# Sheet1.net
KiCad netlist of a schematic drawn in Altium Designer
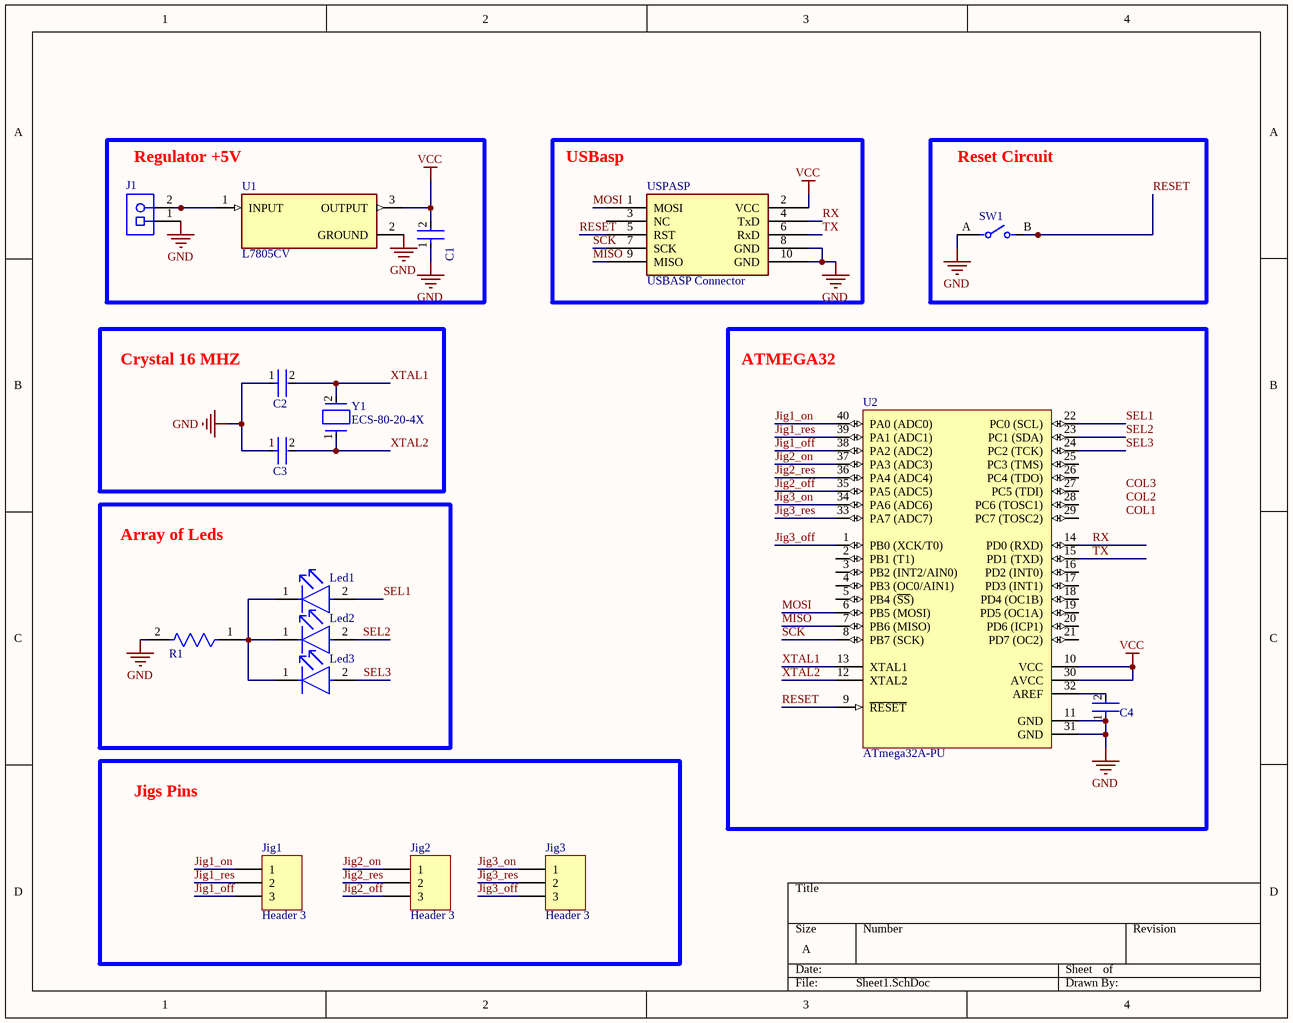
[diagram p0: Sheet1.SchDoc]

(export (version "E")
  (design (tool "Eeschema 10.0.6"))
  (components
    (comp (ref "C1")
      (value "K103K15X7RF5TL2")
      (footprint "FP-K155L2-MFG")
      (description "K103K15X7RF5TL2 Multilayer Ceramic Capacitor, 0.01 uF, 50 V, ± 10%, X7R, Radial Leaded")
      (fields (field (name "VOLTAGE") "50V") (field (name "TOLERANCE") "10%"))
      (libsource (lib "Altium Content Vault") (part "02cd4be3c70576c341d710602a673aa"))
    )
    (comp (ref "C2")
      (value "K103K15X7RF5TL2")
      (footprint "FP-K155L2-MFG")
      (description "K103K15X7RF5TL2 Multilayer Ceramic Capacitor, 0.01 uF, 50 V, ± 10%, X7R, Radial Leaded (10P)")
      (fields (field (name "VOLTAGE") "50V") (field (name "TOLERANCE") "10%"))
      (libsource (lib "Altium Content Vault") (part "02cd4be3c70576c341d710602a673aa"))
    )
    (comp (ref "C3")
      (value "K103K15X7RF5TL2")
      (footprint "FP-K155L2-MFG")
      (description "K103K15X7RF5TL2 Multilayer Ceramic Capacitor, 0.01 uF, 50 V, ± 10%, X7R, Radial Leaded (10P)")
      (fields (field (name "VOLTAGE") "50V") (field (name "TOLERANCE") "10%"))
      (libsource (lib "Altium Content Vault") (part "02cd4be3c70576c341d710602a673aa"))
    )
    (comp (ref "C4")
      (value "K103K15X7RF5TL2")
      (footprint "FP-K155L2-MFG")
      (description "K103K15X7RF5TL2 Multilayer Ceramic Capacitor, 0.01 uF, 50 V, ± 10%, X7R, Radial Leaded")
      (fields (field (name "VOLTAGE") "50V") (field (name "TOLERANCE") "10%"))
      (libsource (lib "Altium Content Vault") (part "02cd4be3c70576c341d710602a673aa"))
    )
    (comp (ref "J1")
      (value "1729128")
      (footprint "PHOE-1729128-2_V")
      (description "Header of  Input Batt")
      (fields (field (name "MANUFACTURER") "Phoenix Contact"))
      (libsource (lib "Altium Content Vault") (part "CN-2P-F-R2"))
    )
    (comp (ref "Jig1")
      (value "Header 3")
      (footprint "HDR1X3")
      (description "Header, 3-Pin")
      (fields (field (name "PUBLISHER") "Altium Limited"))
      (libsource (lib "Miscellaneous+Connectors") (part "Header 3"))
    )
    (comp (ref "Jig2")
      (value "Header 3")
      (footprint "HDR1X3")
      (description "Header, 3-Pin")
      (fields (field (name "PUBLISHER") "Altium Limited"))
      (libsource (lib "Miscellaneous+Connectors") (part "Header 3"))
    )
    (comp (ref "Jig3")
      (value "Header 3")
      (footprint "HDR1X3")
      (description "Header, 3-Pin")
      (fields (field (name "PUBLISHER") "Altium Limited"))
      (libsource (lib "Miscellaneous+Connectors") (part "Header 3"))
    )
    (comp (ref "Led1")
      (value "TLLG4401")
      (footprint "FP-6_544-5255_01-4-MFG")
      (description "TLLG4401 LED, Green, 2mcd, 3mmDia., T-1, +/-25deg, 565nm, 7mA, 1.9V Vf, 20V Vr, 20mW, -40")
      (libsource (lib "Altium Content Vault") (part "8706943c75ba83719d021d2fdc84c58"))
    )
    (comp (ref "Led2")
      (value "TLLG4401")
      (footprint "FP-6_544-5255_01-4-MFG")
      (description "TLLG4401 LED, Green, 2mcd, 3mmDia., T-1, +/-25deg, 565nm, 7mA, 1.9V Vf, 20V Vr, 20mW, -40")
      (libsource (lib "Altium Content Vault") (part "8706943c75ba83719d021d2fdc84c58"))
    )
    (comp (ref "Led3")
      (value "TLLG4401")
      (footprint "FP-6_544-5255_01-4-MFG")
      (description "TLLG4401 LED, Green, 2mcd, 3mmDia., T-1, +/-25deg, 565nm, 7mA, 1.9V Vf, 20V Vr, 20mW, -40")
      (libsource (lib "Altium Content Vault") (part "8706943c75ba83719d021d2fdc84c58"))
    )
    (comp (ref "R1")
      (value "MRS25000C1001FCT00")
      (footprint "FP-MRS25-MFG")
      (description "RES 1K OHM 0.6W 1% for all leds")
      (fields (field (name "TOLERANCE") "1%"))
      (libsource (lib "Altium Content Vault") (part "1029c3af85768c4190bb7ad29bc67b5"))
    )
    (comp (ref "SW1")
      (value "EVQ-21505R")
      (footprint "FP-EVQ-21505R-MFG")
      (description "Switch for reset circuits")
      (libsource (lib "Altium Content Vault") (part "2b0b2b19372efd94fa7681498149756"))
    )
    (comp (ref "U1")
      (value "L7805CV")
      (footprint "TO255P1040X460X1968-3")
      (description "Linear Voltage Regulator IC Positive Fixed 1 Output 1.5A TO-220")
      (fields (field (name "MF") "STMicroelectronics"))
      (libsource (lib "L7805CV") (part "L7805CV"))
    )
    (comp (ref "U2")
      (value "ATmega32A-PU")
      (footprint "40P6")
      (libsource (lib "Altium Content Vault") (part "MC-8B-AT16A-IL40"))
    )
    (comp (ref "USPASP")
      (value "USBASP Connector")
      (footprint "SHDR10W99P254_2X5_2032X889X927P")
      (description "Connector")
      (fields
        (field (name "MANUFACTURER_PART_NUMBER") "70246-1001")
        (field (name "MOUSER PART NUMBER") "538-70246-1001")
      )
      (libsource (lib "YoussifLIB") (part "USBASP Connector"))
    )
    (comp (ref "Y1")
      (value "ECS-80-20-4X")
      (footprint "FP-ECS-80-20-4X-MFG")
      (fields (field (name "TOLERANCE") "0.003%"))
      (libsource (lib "Altium Content Vault") (part "c23a69dc6c9e2f18f2079038eb95dd1"))
    )
  )
  (nets
    (net (code "4") (name "/Jig1_off") (class "Default")
      (node (ref "Jig1") (pin "3") (pinfunction "3_3") (pintype "passive"))
      (node (ref "U2") (pin "38") (pinfunction "PA2_(ADC2)_38") (pintype "bidirectional"))
    )
    (net (code "5") (name "/Jig1_on") (class "Default")
      (node (ref "Jig1") (pin "1") (pinfunction "1_1") (pintype "passive"))
      (node (ref "U2") (pin "40") (pinfunction "PA0_(ADC0)_40") (pintype "bidirectional"))
    )
    (net (code "6") (name "/Jig1_res") (class "Default")
      (node (ref "Jig1") (pin "2") (pinfunction "2_2") (pintype "passive"))
      (node (ref "U2") (pin "39") (pinfunction "PA1_(ADC1)_39") (pintype "bidirectional"))
    )
    (net (code "7") (name "/Jig2_off") (class "Default")
      (node (ref "Jig2") (pin "3") (pinfunction "3_3") (pintype "passive"))
      (node (ref "U2") (pin "35") (pinfunction "PA5_(ADC5)_35") (pintype "bidirectional"))
    )
    (net (code "8") (name "/Jig2_on") (class "Default")
      (node (ref "Jig2") (pin "1") (pinfunction "1_1") (pintype "passive"))
      (node (ref "U2") (pin "37") (pinfunction "PA3_(ADC3)_37") (pintype "bidirectional"))
    )
    (net (code "9") (name "/Jig2_res") (class "Default")
      (node (ref "Jig2") (pin "2") (pinfunction "2_2") (pintype "passive"))
      (node (ref "U2") (pin "36") (pinfunction "PA4_(ADC4)_36") (pintype "bidirectional"))
    )
    (net (code "10") (name "/Jig3_off") (class "Default")
      (node (ref "Jig3") (pin "3") (pinfunction "3_3") (pintype "passive"))
      (node (ref "U2") (pin "1") (pinfunction "PB0_(XCK/T0)_1") (pintype "bidirectional"))
    )
    (net (code "11") (name "/Jig3_on") (class "Default")
      (node (ref "Jig3") (pin "1") (pinfunction "1_1") (pintype "passive"))
      (node (ref "U2") (pin "34") (pinfunction "PA6_(ADC6)_34") (pintype "bidirectional"))
    )
    (net (code "12") (name "/Jig3_res") (class "Default")
      (node (ref "Jig3") (pin "2") (pinfunction "2_2") (pintype "passive"))
      (node (ref "U2") (pin "33") (pinfunction "PA7_(ADC7)_33") (pintype "bidirectional"))
    )
    (net (code "13") (name "/MISO") (class "Default")
      (node (ref "U2") (pin "7") (pinfunction "PB6_(MISO)_7") (pintype "bidirectional"))
      (node (ref "USPASP") (pin "9") (pinfunction "MISO_9") (pintype "passive"))
    )
    (net (code "14") (name "/MOSI") (class "Default")
      (node (ref "U2") (pin "6") (pinfunction "PB5_(MOSI)_6") (pintype "bidirectional"))
      (node (ref "USPASP") (pin "1") (pinfunction "MOSI_1") (pintype "passive"))
    )
    (net (code "15") (name "/RESET") (class "Default")
      (node (ref "SW1") (pin "B") (pinfunction "B_B") (pintype "passive"))
      (node (ref "U2") (pin "9") (pinfunction "~{RESET}_9") (pintype "input"))
      (node (ref "USPASP") (pin "5") (pinfunction "RST_5") (pintype "passive"))
    )
    (net (code "16") (name "/RX") (class "Default")
      (node (ref "U2") (pin "14") (pinfunction "PD0_(RXD)_14") (pintype "bidirectional"))
      (node (ref "USPASP") (pin "4") (pinfunction "TxD_4") (pintype "passive"))
    )
    (net (code "17") (name "/SCK") (class "Default")
      (node (ref "U2") (pin "8") (pinfunction "PB7_(SCK)_8") (pintype "bidirectional"))
      (node (ref "USPASP") (pin "7") (pinfunction "SCK_7") (pintype "passive"))
    )
    (net (code "18") (name "/SEL1") (class "Default")
      (node (ref "Led1") (pin "2") (pinfunction "A_2") (pintype "passive"))
      (node (ref "U2") (pin "22") (pinfunction "PC0_(SCL)_22") (pintype "bidirectional"))
    )
    (net (code "19") (name "/SEL2") (class "Default")
      (node (ref "Led2") (pin "2") (pinfunction "A_2") (pintype "passive"))
      (node (ref "U2") (pin "23") (pinfunction "PC1_(SDA)_23") (pintype "bidirectional"))
    )
    (net (code "20") (name "/SEL3") (class "Default")
      (node (ref "Led3") (pin "2") (pinfunction "A_2") (pintype "passive"))
      (node (ref "U2") (pin "24") (pinfunction "PC2_(TCK)_24") (pintype "bidirectional"))
    )
    (net (code "21") (name "/TX") (class "Default")
      (node (ref "U2") (pin "15") (pinfunction "PD1_(TXD)_15") (pintype "bidirectional"))
      (node (ref "USPASP") (pin "6") (pinfunction "RxD_6") (pintype "passive"))
    )
    (net (code "22") (name "/XTAL1") (class "Default")
      (node (ref "C2") (pin "2") (pinfunction "2_2") (pintype "passive"))
      (node (ref "U2") (pin "13") (pinfunction "XTAL1_13") (pintype "passive"))
      (node (ref "Y1") (pin "2") (pinfunction "2_2") (pintype "passive"))
    )
    (net (code "23") (name "/XTAL2") (class "Default")
      (node (ref "C3") (pin "2") (pinfunction "2_2") (pintype "passive"))
      (node (ref "U2") (pin "12") (pinfunction "XTAL2_12") (pintype "passive"))
      (node (ref "Y1") (pin "1") (pinfunction "1_1") (pintype "passive"))
    )
    (net (code "24") (name "GND") (class "Default")
      (node (ref "C1") (pin "1") (pinfunction "1_1") (pintype "passive"))
      (node (ref "C2") (pin "1") (pinfunction "1_1") (pintype "passive"))
      (node (ref "C3") (pin "1") (pinfunction "1_1") (pintype "passive"))
      (node (ref "C4") (pin "1") (pinfunction "1_1") (pintype "passive"))
      (node (ref "J1") (pin "1") (pinfunction "1_1") (pintype "passive"))
      (node (ref "R1") (pin "2") (pinfunction "2_2") (pintype "passive"))
      (node (ref "SW1") (pin "A") (pinfunction "A_A") (pintype "passive"))
      (node (ref "U1") (pin "2") (pinfunction "GROUND_2") (pintype "power_in"))
      (node (ref "U2") (pin "11") (pinfunction "GND_11") (pintype "power_in"))
      (node (ref "U2") (pin "31") (pinfunction "GND_31") (pintype "power_in"))
      (node (ref "USPASP") (pin "10") (pinfunction "GND_10") (pintype "passive"))
      (node (ref "USPASP") (pin "8") (pinfunction "GND_8") (pintype "passive"))
    )
    (net (code "25") (name "Net-(Led1-C)") (class "Default")
      (node (ref "Led1") (pin "1") (pinfunction "C_1") (pintype "passive"))
      (node (ref "Led2") (pin "1") (pinfunction "C_1") (pintype "passive"))
      (node (ref "Led3") (pin "1") (pinfunction "C_1") (pintype "passive"))
      (node (ref "R1") (pin "1") (pinfunction "1_1") (pintype "passive"))
    )
    (net (code "26") (name "Net-(U1-INPUT)") (class "Default")
      (node (ref "J1") (pin "2") (pinfunction "2_2") (pintype "passive"))
      (node (ref "U1") (pin "1") (pinfunction "INPUT_1") (pintype "input"))
    )
    (net (code "27") (name "Net-(U2-AREF)") (class "Default")
      (node (ref "C4") (pin "2") (pinfunction "2_2") (pintype "passive"))
      (node (ref "U2") (pin "32") (pinfunction "AREF_32") (pintype "power_in"))
    )
    (net (code "28") (name "VCC") (class "Default")
      (node (ref "C1") (pin "2") (pinfunction "2_2") (pintype "passive"))
      (node (ref "U1") (pin "3") (pinfunction "OUTPUT_3") (pintype "output"))
      (node (ref "U2") (pin "10") (pinfunction "VCC_10") (pintype "power_in"))
      (node (ref "U2") (pin "30") (pinfunction "AVCC_30") (pintype "power_in"))
      (node (ref "USPASP") (pin "2") (pinfunction "VCC_2") (pintype "passive"))
    )
    (net (code "29") (name "unconnected-(U2-PB1_(T1)-Pad2)") (class "Default")
      (node (ref "U2") (pin "2") (pinfunction "PB1_(T1)_2") (pintype "bidirectional"))
    )
    (net (code "30") (name "unconnected-(U2-PB2_(INT2{slash}AIN0)-Pad3)") (class "Default")
      (node (ref "U2") (pin "3") (pinfunction "PB2_(INT2/AIN0)_3") (pintype "bidirectional"))
    )
    (net (code "31") (name "unconnected-(U2-PB3_(OC0{slash}AIN1)-Pad4)") (class "Default")
      (node (ref "U2") (pin "4") (pinfunction "PB3_(OC0/AIN1)_4") (pintype "bidirectional"))
    )
    (net (code "32") (name "unconnected-(U2-PB4_(~{SS})-Pad5)") (class "Default")
      (node (ref "U2") (pin "5") (pinfunction "PB4_(~{SS})_5") (pintype "bidirectional"))
    )
    (net (code "33") (name "unconnected-(U2-PC3_(TMS)-Pad25)") (class "Default")
      (node (ref "U2") (pin "25") (pinfunction "PC3_(TMS)_25") (pintype "bidirectional"))
    )
    (net (code "34") (name "unconnected-(U2-PC4_(TDO)-Pad26)") (class "Default")
      (node (ref "U2") (pin "26") (pinfunction "PC4_(TDO)_26") (pintype "bidirectional"))
    )
    (net (code "35") (name "unconnected-(U2-PC5_(TDI)-Pad27)") (class "Default")
      (node (ref "U2") (pin "27") (pinfunction "PC5_(TDI)_27") (pintype "bidirectional"))
    )
    (net (code "36") (name "unconnected-(U2-PC6_(TOSC1)-Pad28)") (class "Default")
      (node (ref "U2") (pin "28") (pinfunction "PC6_(TOSC1)_28") (pintype "bidirectional"))
    )
    (net (code "37") (name "unconnected-(U2-PC7_(TOSC2)-Pad29)") (class "Default")
      (node (ref "U2") (pin "29") (pinfunction "PC7_(TOSC2)_29") (pintype "bidirectional"))
    )
    (net (code "38") (name "unconnected-(U2-PD2_(INT0)-Pad16)") (class "Default")
      (node (ref "U2") (pin "16") (pinfunction "PD2_(INT0)_16") (pintype "bidirectional"))
    )
    (net (code "39") (name "unconnected-(U2-PD3_(INT1)-Pad17)") (class "Default")
      (node (ref "U2") (pin "17") (pinfunction "PD3_(INT1)_17") (pintype "bidirectional"))
    )
    (net (code "40") (name "unconnected-(U2-PD4_(OC1B)-Pad18)") (class "Default")
      (node (ref "U2") (pin "18") (pinfunction "PD4_(OC1B)_18") (pintype "bidirectional"))
    )
    (net (code "41") (name "unconnected-(U2-PD5_(OC1A)-Pad19)") (class "Default")
      (node (ref "U2") (pin "19") (pinfunction "PD5_(OC1A)_19") (pintype "bidirectional"))
    )
    (net (code "42") (name "unconnected-(U2-PD6_(ICP1)-Pad20)") (class "Default")
      (node (ref "U2") (pin "20") (pinfunction "PD6_(ICP1)_20") (pintype "bidirectional"))
    )
    (net (code "43") (name "unconnected-(U2-PD7_(OC2)-Pad21)") (class "Default")
      (node (ref "U2") (pin "21") (pinfunction "PD7_(OC2)_21") (pintype "bidirectional"))
    )
    (net (code "44") (name "unconnected-(USPASP-NC-Pad3)") (class "Default")
      (node (ref "USPASP") (pin "3") (pinfunction "NC_3") (pintype "passive"))
    )
  )
)
